# Mechanical.net
KiCad netlist of a schematic drawn in Altium Designer
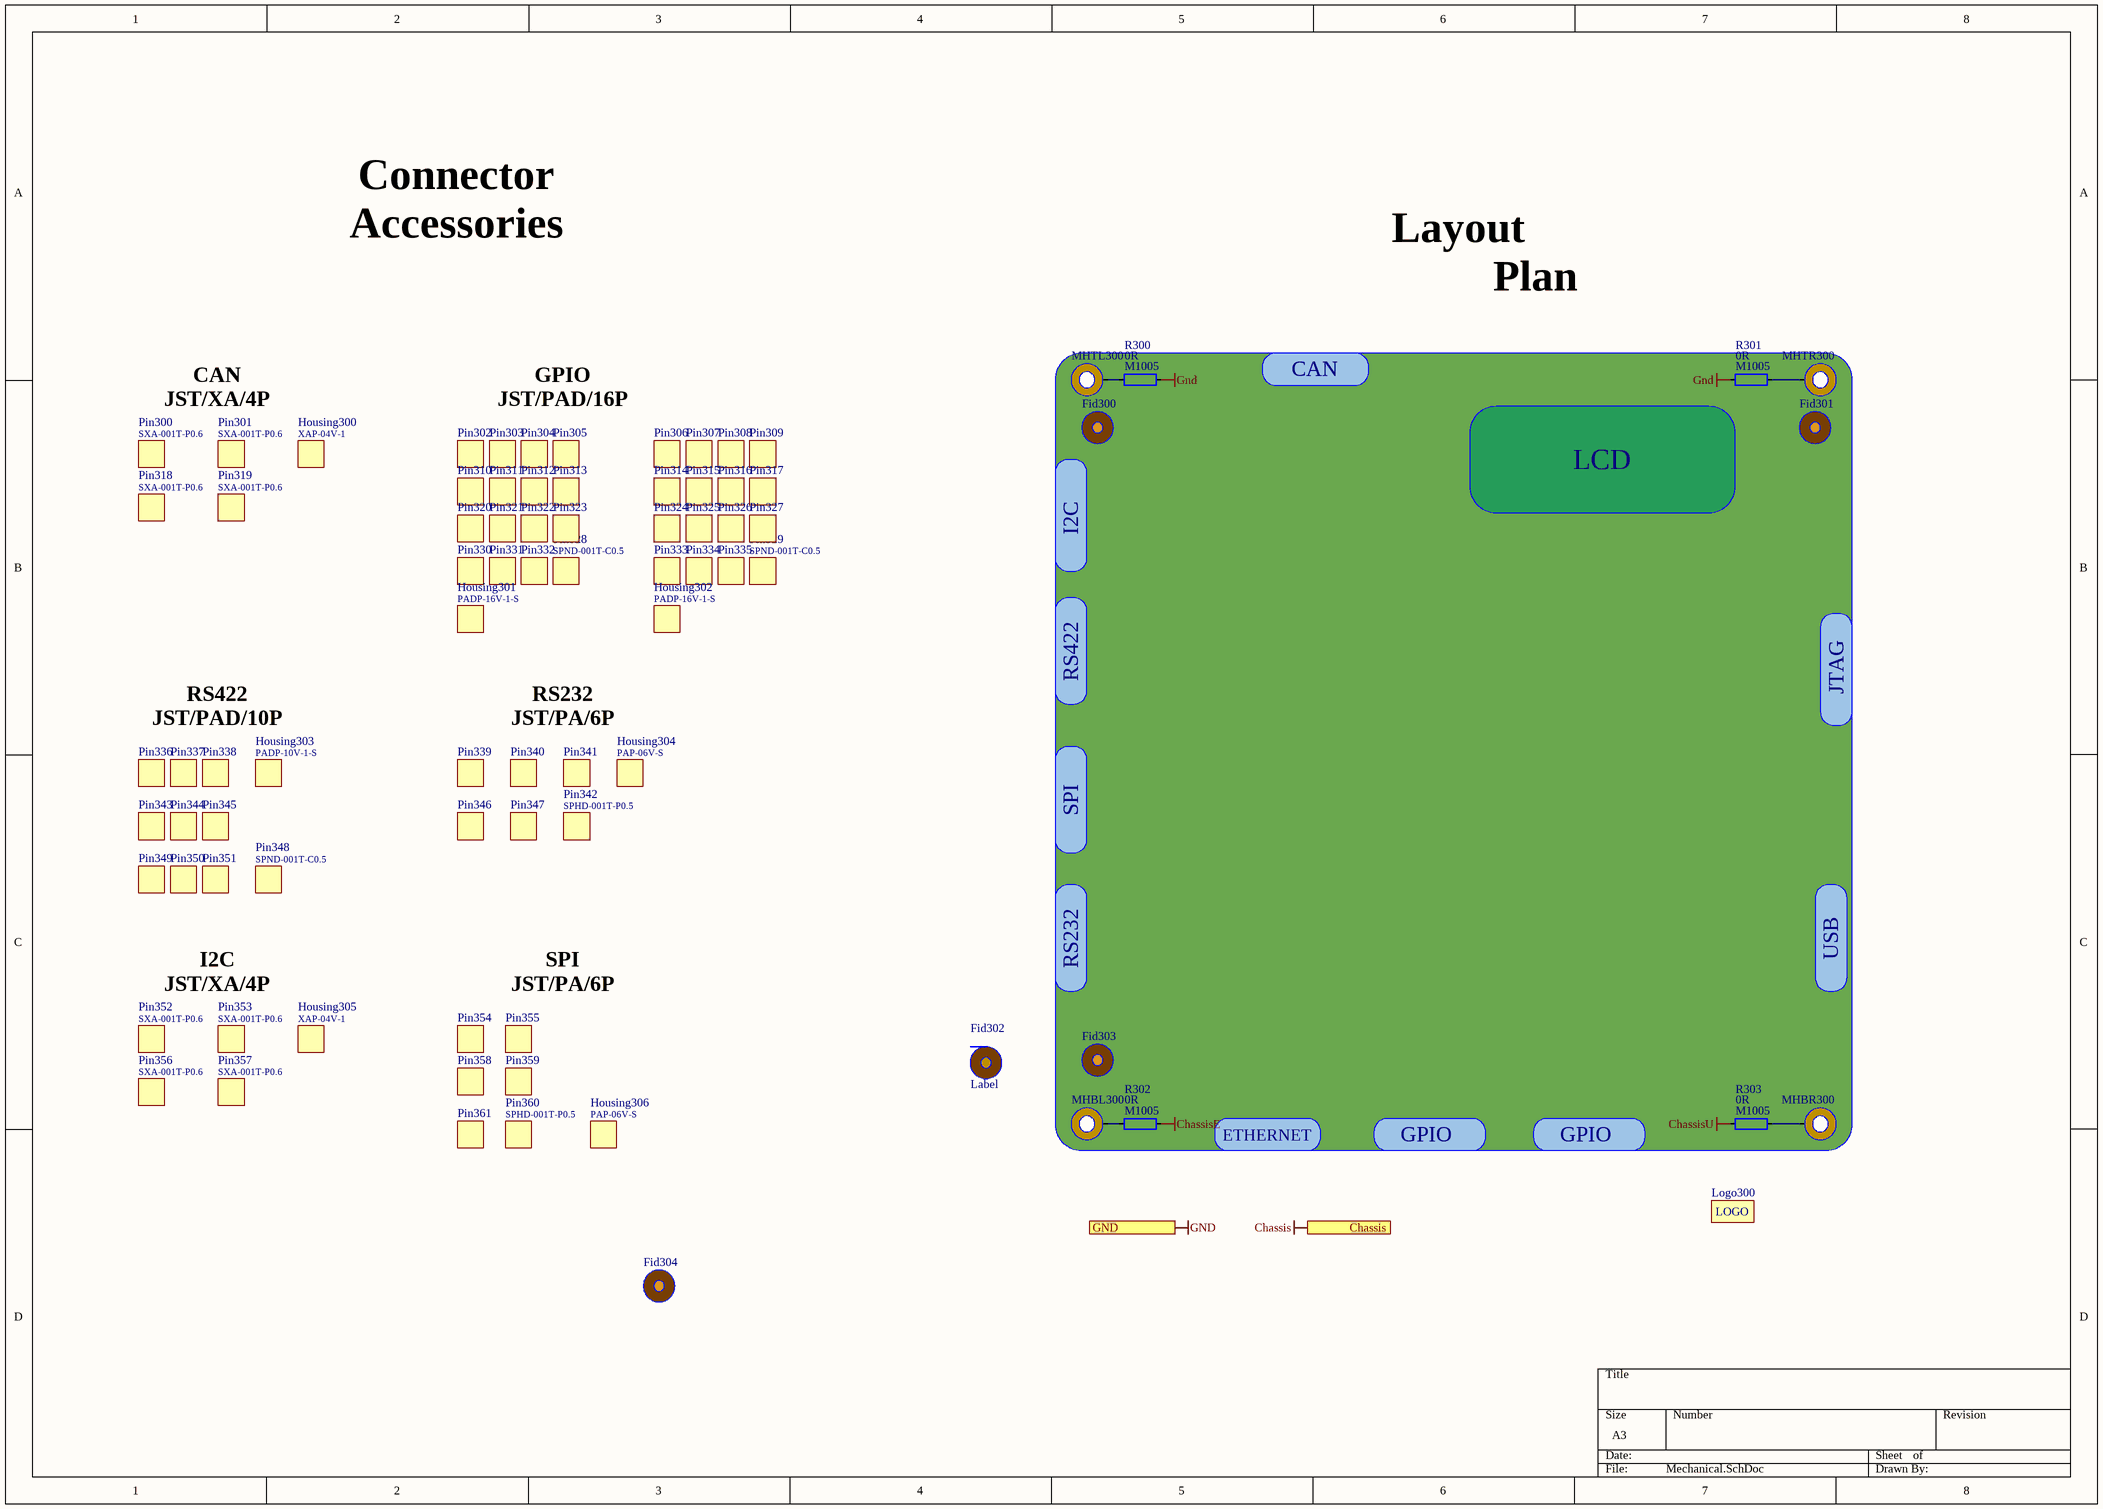
[diagram p0: Mechanical.SchDoc]

(export (version "E")
  (design (tool "Eeschema 10.0.6"))
  (components
    (comp (ref "Fid300")
      (value "Fiducial")
      (footprint "Fiducial - 2mm, 5mm")
      (description "Mechanical, Fiducial, PCB, 2mm/5mm")
      (libsource (lib "Mechanical") (part "Fiducial"))
    )
    (comp (ref "Fid301")
      (value "Fiducial")
      (footprint "Fiducial - 2mm, 5mm")
      (description "Mechanical, Fiducial, PCB, 2mm/5mm")
      (libsource (lib "Mechanical") (part "Fiducial"))
    )
    (comp (ref "Fid302")
      (value "Fiducial")
      (footprint "Fiducial-2mm,5mm")
      (description "IC,Interface,FTDI,QFN16")
      (fields (field (name "MANUFACTURER") "FTDI") (field (name "LABEL") "Label"))
      (libsource (lib "") (part "Fiducial_1"))
    )
    (comp (ref "Fid303")
      (value "Fiducial")
      (footprint "Fiducial - 2mm, 5mm")
      (description "Mechanical, Fiducial, PCB, 2mm/5mm")
      (libsource (lib "Mechanical") (part "Fiducial"))
    )
    (comp (ref "Fid304")
      (value "Fiducial")
      (footprint "Fiducial - 2mm, 5mm")
      (description "Mechanical, Fiducial, PCB, 2mm/5mm")
      (libsource (lib "Mechanical") (part "Fiducial"))
    )
    (comp (ref "Housing300")
      (value "Housing")
      (footprint "Housing, PAP-06V-S")
      (description "Housing, JST, 4P, XA")
      (fields (field (name "MANUFACTURER") "JST") (field (name "MANUFACTURER PART NUMBER") "XAP-04V-1"))
      (libsource (lib "Connector - JST") (part "Housing"))
    )
    (comp (ref "Housing301")
      (value "Housing")
      (footprint "Housing, PADP-16V-1-S")
      (description "Housing, JST, 16P, PAD")
      (fields (field (name "MANUFACTURER") "JST") (field (name "MANUFACTURER PART NUMBER") "PADP-16V-1-S"))
      (libsource (lib "Connector - JST") (part "Housing"))
    )
    (comp (ref "Housing302")
      (value "Housing")
      (footprint "Housing, PADP-16V-1-S")
      (description "Housing, JST, 16P, PAD")
      (fields (field (name "MANUFACTURER") "JST") (field (name "MANUFACTURER PART NUMBER") "PADP-16V-1-S"))
      (libsource (lib "Connector - JST") (part "Housing"))
    )
    (comp (ref "Housing303")
      (value "Housing")
      (footprint "Housing, PADP-10V-1-S")
      (description "Housing, JST, 10P, PAD")
      (fields (field (name "MANUFACTURER") "JST") (field (name "MANUFACTURER PART NUMBER") "PADP-10V-1-S"))
      (libsource (lib "Connector - JST") (part "Housing"))
    )
    (comp (ref "Housing304")
      (value "Housing")
      (footprint "Housing, PAP-06V-S")
      (description "Housing, JST, PAP-06V-S")
      (fields (field (name "MANUFACTURER") "JST") (field (name "MANUFACTURER PART NUMBER") "PAP-06V-S"))
      (libsource (lib "Connector - JST") (part "Housing"))
    )
    (comp (ref "Housing305")
      (value "Housing")
      (footprint "Housing, PAP-06V-S")
      (description "Housing, JST, 4P, XA")
      (fields (field (name "MANUFACTURER") "JST") (field (name "MANUFACTURER PART NUMBER") "XAP-04V-1"))
      (libsource (lib "Connector - JST") (part "Housing"))
    )
    (comp (ref "Housing306")
      (value "Housing")
      (footprint "Housing, PAP-06V-S")
      (description "IC, Interface, FTDI, QFN-16")
      (fields (field (name "MANUFACTURER") "JST") (field (name "MANUFACTURER PART NUMBER") "PAP-06V-S"))
      (libsource (lib "Connector - JST") (part "Housing"))
    )
    (comp (ref "Logo300")
      (value "Logo")
      (footprint "Logo 1")
      (description "Mechanical, Logo")
      (libsource (lib "Mechanical") (part "Logo"))
    )
    (comp (ref "MHBL300")
      (value "Mounting Hole")
      (footprint "Mounting Hole - Hole-3.2mm, Pad-5mm")
      (description "Mechanical, Mounting Hole")
      (libsource (lib "Mechanical") (part "Mounting Hole"))
    )
    (comp (ref "MHBR300")
      (value "Mounting Hole")
      (footprint "Mounting Hole - Hole-3.2mm, Pad-5mm")
      (description "Mechanical, Mounting Hole")
      (libsource (lib "Mechanical") (part "Mounting Hole"))
    )
    (comp (ref "MHTL300")
      (value "Mounting Hole")
      (footprint "Mounting Hole - Hole-3.2mm, Pad-5mm")
      (description "Mechanical, Mounting Hole")
      (libsource (lib "Mechanical") (part "Mounting Hole"))
    )
    (comp (ref "MHTR300")
      (value "Mounting Hole")
      (footprint "Mounting Hole - Hole-3.2mm, Pad-5mm")
      (description "Mechanical, Mounting Hole")
      (libsource (lib "Mechanical") (part "Mounting Hole"))
    )
    (comp (ref "Pin300")
      (value "Pin")
      (footprint "Pin, SPHD-001T-P0.5")
      (description "Pin, JST, SXA-001T-P0.6")
      (fields (field (name "MANUFACTURER") "JST") (field (name "MANUFACTURER PART NUMBER") "SXA-001T-P0.6"))
      (libsource (lib "Connector - JST") (part "Pin"))
    )
    (comp (ref "Pin301")
      (value "Pin")
      (footprint "Pin, SPHD-001T-P0.5")
      (description "Pin, JST, SXA-001T-P0.6")
      (fields (field (name "MANUFACTURER") "JST") (field (name "MANUFACTURER PART NUMBER") "SXA-001T-P0.6"))
      (libsource (lib "Connector - JST") (part "Pin"))
    )
    (comp (ref "Pin302")
      (value "Pin")
      (footprint "Pin, SPND-001T-C0.5")
      (description "Pin, JST, SPND-001T-C0.5")
      (fields (field (name "MANUFACTURER") "JST") (field (name "MANUFACTURER PART NUMBER") "SPND-001T-C0.5"))
      (libsource (lib "Connector - JST") (part "Pin"))
    )
    (comp (ref "Pin303")
      (value "Pin")
      (footprint "Pin, SPND-001T-C0.5")
      (description "Pin, JST, SPND-001T-C0.5")
      (fields (field (name "MANUFACTURER") "JST") (field (name "MANUFACTURER PART NUMBER") "SPND-001T-C0.5"))
      (libsource (lib "Connector - JST") (part "Pin"))
    )
    (comp (ref "Pin304")
      (value "Pin")
      (footprint "Pin, SPND-001T-C0.5")
      (description "Pin, JST, SPND-001T-C0.5")
      (fields (field (name "MANUFACTURER") "JST") (field (name "MANUFACTURER PART NUMBER") "SPND-001T-C0.5"))
      (libsource (lib "Connector - JST") (part "Pin"))
    )
    (comp (ref "Pin305")
      (value "Pin")
      (footprint "Pin, SPND-001T-C0.5")
      (description "Pin, JST, SPND-001T-C0.5")
      (fields (field (name "MANUFACTURER") "JST") (field (name "MANUFACTURER PART NUMBER") "SPND-001T-C0.5"))
      (libsource (lib "Connector - JST") (part "Pin"))
    )
    (comp (ref "Pin306")
      (value "Pin")
      (footprint "Pin, SPND-001T-C0.5")
      (description "Pin, JST, SPND-001T-C0.5")
      (fields (field (name "MANUFACTURER") "JST") (field (name "MANUFACTURER PART NUMBER") "SPND-001T-C0.5"))
      (libsource (lib "Connector - JST") (part "Pin"))
    )
    (comp (ref "Pin307")
      (value "Pin")
      (footprint "Pin, SPND-001T-C0.5")
      (description "Pin, JST, SPND-001T-C0.5")
      (fields (field (name "MANUFACTURER") "JST") (field (name "MANUFACTURER PART NUMBER") "SPND-001T-C0.5"))
      (libsource (lib "Connector - JST") (part "Pin"))
    )
    (comp (ref "Pin308")
      (value "Pin")
      (footprint "Pin, SPND-001T-C0.5")
      (description "Pin, JST, SPND-001T-C0.5")
      (fields (field (name "MANUFACTURER") "JST") (field (name "MANUFACTURER PART NUMBER") "SPND-001T-C0.5"))
      (libsource (lib "Connector - JST") (part "Pin"))
    )
    (comp (ref "Pin309")
      (value "Pin")
      (footprint "Pin, SPND-001T-C0.5")
      (description "Pin, JST, SPND-001T-C0.5")
      (fields (field (name "MANUFACTURER") "JST") (field (name "MANUFACTURER PART NUMBER") "SPND-001T-C0.5"))
      (libsource (lib "Connector - JST") (part "Pin"))
    )
    (comp (ref "Pin310")
      (value "Pin")
      (footprint "Pin, SPND-001T-C0.5")
      (description "Pin, JST, SPND-001T-C0.5")
      (fields (field (name "MANUFACTURER") "JST") (field (name "MANUFACTURER PART NUMBER") "SPND-001T-C0.5"))
      (libsource (lib "Connector - JST") (part "Pin"))
    )
    (comp (ref "Pin311")
      (value "Pin")
      (footprint "Pin, SPND-001T-C0.5")
      (description "Pin, JST, SPND-001T-C0.5")
      (fields (field (name "MANUFACTURER") "JST") (field (name "MANUFACTURER PART NUMBER") "SPND-001T-C0.5"))
      (libsource (lib "Connector - JST") (part "Pin"))
    )
    (comp (ref "Pin312")
      (value "Pin")
      (footprint "Pin, SPND-001T-C0.5")
      (description "Pin, JST, SPND-001T-C0.5")
      (fields (field (name "MANUFACTURER") "JST") (field (name "MANUFACTURER PART NUMBER") "SPND-001T-C0.5"))
      (libsource (lib "Connector - JST") (part "Pin"))
    )
    (comp (ref "Pin313")
      (value "Pin")
      (footprint "Pin, SPND-001T-C0.5")
      (description "Pin, JST, SPND-001T-C0.5")
      (fields (field (name "MANUFACTURER") "JST") (field (name "MANUFACTURER PART NUMBER") "SPND-001T-C0.5"))
      (libsource (lib "Connector - JST") (part "Pin"))
    )
    (comp (ref "Pin314")
      (value "Pin")
      (footprint "Pin, SPND-001T-C0.5")
      (description "Pin, JST, SPND-001T-C0.5")
      (fields (field (name "MANUFACTURER") "JST") (field (name "MANUFACTURER PART NUMBER") "SPND-001T-C0.5"))
      (libsource (lib "Connector - JST") (part "Pin"))
    )
    (comp (ref "Pin315")
      (value "Pin")
      (footprint "Pin, SPND-001T-C0.5")
      (description "Pin, JST, SPND-001T-C0.5")
      (fields (field (name "MANUFACTURER") "JST") (field (name "MANUFACTURER PART NUMBER") "SPND-001T-C0.5"))
      (libsource (lib "Connector - JST") (part "Pin"))
    )
    (comp (ref "Pin316")
      (value "Pin")
      (footprint "Pin, SPND-001T-C0.5")
      (description "Pin, JST, SPND-001T-C0.5")
      (fields (field (name "MANUFACTURER") "JST") (field (name "MANUFACTURER PART NUMBER") "SPND-001T-C0.5"))
      (libsource (lib "Connector - JST") (part "Pin"))
    )
    (comp (ref "Pin317")
      (value "Pin")
      (footprint "Pin, SPND-001T-C0.5")
      (description "Pin, JST, SPND-001T-C0.5")
      (fields (field (name "MANUFACTURER") "JST") (field (name "MANUFACTURER PART NUMBER") "SPND-001T-C0.5"))
      (libsource (lib "Connector - JST") (part "Pin"))
    )
    (comp (ref "Pin318")
      (value "Pin")
      (footprint "Pin, SPHD-001T-P0.5")
      (description "Pin, JST, SXA-001T-P0.6")
      (fields (field (name "MANUFACTURER") "JST") (field (name "MANUFACTURER PART NUMBER") "SXA-001T-P0.6"))
      (libsource (lib "Connector - JST") (part "Pin"))
    )
    (comp (ref "Pin319")
      (value "Pin")
      (footprint "Pin, SPHD-001T-P0.5")
      (description "Pin, JST, SXA-001T-P0.6")
      (fields (field (name "MANUFACTURER") "JST") (field (name "MANUFACTURER PART NUMBER") "SXA-001T-P0.6"))
      (libsource (lib "Connector - JST") (part "Pin"))
    )
    (comp (ref "Pin320")
      (value "Pin")
      (footprint "Pin, SPND-001T-C0.5")
      (description "Pin, JST, SPND-001T-C0.5")
      (fields (field (name "MANUFACTURER") "JST") (field (name "MANUFACTURER PART NUMBER") "SPND-001T-C0.5"))
      (libsource (lib "Connector - JST") (part "Pin"))
    )
    (comp (ref "Pin321")
      (value "Pin")
      (footprint "Pin, SPND-001T-C0.5")
      (description "Pin, JST, SPND-001T-C0.5")
      (fields (field (name "MANUFACTURER") "JST") (field (name "MANUFACTURER PART NUMBER") "SPND-001T-C0.5"))
      (libsource (lib "Connector - JST") (part "Pin"))
    )
    (comp (ref "Pin322")
      (value "Pin")
      (footprint "Pin, SPND-001T-C0.5")
      (description "Pin, JST, SPND-001T-C0.5")
      (fields (field (name "MANUFACTURER") "JST") (field (name "MANUFACTURER PART NUMBER") "SPND-001T-C0.5"))
      (libsource (lib "Connector - JST") (part "Pin"))
    )
    (comp (ref "Pin323")
      (value "Pin")
      (footprint "Pin, SPND-001T-C0.5")
      (description "Pin, JST, SPND-001T-C0.5")
      (fields (field (name "MANUFACTURER") "JST") (field (name "MANUFACTURER PART NUMBER") "SPND-001T-C0.5"))
      (libsource (lib "Connector - JST") (part "Pin"))
    )
    (comp (ref "Pin324")
      (value "Pin")
      (footprint "Pin, SPND-001T-C0.5")
      (description "Pin, JST, SPND-001T-C0.5")
      (fields (field (name "MANUFACTURER") "JST") (field (name "MANUFACTURER PART NUMBER") "SPND-001T-C0.5"))
      (libsource (lib "Connector - JST") (part "Pin"))
    )
    (comp (ref "Pin325")
      (value "Pin")
      (footprint "Pin, SPND-001T-C0.5")
      (description "Pin, JST, SPND-001T-C0.5")
      (fields (field (name "MANUFACTURER") "JST") (field (name "MANUFACTURER PART NUMBER") "SPND-001T-C0.5"))
      (libsource (lib "Connector - JST") (part "Pin"))
    )
    (comp (ref "Pin326")
      (value "Pin")
      (footprint "Pin, SPND-001T-C0.5")
      (description "Pin, JST, SPND-001T-C0.5")
      (fields (field (name "MANUFACTURER") "JST") (field (name "MANUFACTURER PART NUMBER") "SPND-001T-C0.5"))
      (libsource (lib "Connector - JST") (part "Pin"))
    )
    (comp (ref "Pin327")
      (value "Pin")
      (footprint "Pin, SPND-001T-C0.5")
      (description "Pin, JST, SPND-001T-C0.5")
      (fields (field (name "MANUFACTURER") "JST") (field (name "MANUFACTURER PART NUMBER") "SPND-001T-C0.5"))
      (libsource (lib "Connector - JST") (part "Pin"))
    )
    (comp (ref "Pin328")
      (value "Pin")
      (footprint "Pin, SPND-001T-C0.5")
      (description "Pin, JST, SPND-001T-C0.5")
      (fields (field (name "MANUFACTURER") "JST") (field (name "MANUFACTURER PART NUMBER") "SPND-001T-C0.5"))
      (libsource (lib "Connector - JST") (part "Pin"))
    )
    (comp (ref "Pin329")
      (value "Pin")
      (footprint "Pin, SPND-001T-C0.5")
      (description "Pin, JST, SPND-001T-C0.5")
      (fields (field (name "MANUFACTURER") "JST") (field (name "MANUFACTURER PART NUMBER") "SPND-001T-C0.5"))
      (libsource (lib "Connector - JST") (part "Pin"))
    )
    (comp (ref "Pin330")
      (value "Pin")
      (footprint "Pin, SPND-001T-C0.5")
      (description "Pin, JST, SPND-001T-C0.5")
      (fields (field (name "MANUFACTURER") "JST") (field (name "MANUFACTURER PART NUMBER") "SPND-001T-C0.5"))
      (libsource (lib "Connector - JST") (part "Pin"))
    )
    (comp (ref "Pin331")
      (value "Pin")
      (footprint "Pin, SPND-001T-C0.5")
      (description "Pin, JST, SPND-001T-C0.5")
      (fields (field (name "MANUFACTURER") "JST") (field (name "MANUFACTURER PART NUMBER") "SPND-001T-C0.5"))
      (libsource (lib "Connector - JST") (part "Pin"))
    )
    (comp (ref "Pin332")
      (value "Pin")
      (footprint "Pin, SPND-001T-C0.5")
      (description "Pin, JST, SPND-001T-C0.5")
      (fields (field (name "MANUFACTURER") "JST") (field (name "MANUFACTURER PART NUMBER") "SPND-001T-C0.5"))
      (libsource (lib "Connector - JST") (part "Pin"))
    )
    (comp (ref "Pin333")
      (value "Pin")
      (footprint "Pin, SPND-001T-C0.5")
      (description "Pin, JST, SPND-001T-C0.5")
      (fields (field (name "MANUFACTURER") "JST") (field (name "MANUFACTURER PART NUMBER") "SPND-001T-C0.5"))
      (libsource (lib "Connector - JST") (part "Pin"))
    )
    (comp (ref "Pin334")
      (value "Pin")
      (footprint "Pin, SPND-001T-C0.5")
      (description "Pin, JST, SPND-001T-C0.5")
      (fields (field (name "MANUFACTURER") "JST") (field (name "MANUFACTURER PART NUMBER") "SPND-001T-C0.5"))
      (libsource (lib "Connector - JST") (part "Pin"))
    )
    (comp (ref "Pin335")
      (value "Pin")
      (footprint "Pin, SPND-001T-C0.5")
      (description "Pin, JST, SPND-001T-C0.5")
      (fields (field (name "MANUFACTURER") "JST") (field (name "MANUFACTURER PART NUMBER") "SPND-001T-C0.5"))
      (libsource (lib "Connector - JST") (part "Pin"))
    )
    (comp (ref "Pin336")
      (value "Pin")
      (footprint "Pin, SPND-001T-C0.5")
      (description "Pin, JST, SPND-001T-C0.5")
      (fields (field (name "MANUFACTURER") "JST") (field (name "MANUFACTURER PART NUMBER") "SPND-001T-C0.5"))
      (libsource (lib "Connector - JST") (part "Pin"))
    )
    (comp (ref "Pin337")
      (value "Pin")
      (footprint "Pin, SPND-001T-C0.5")
      (description "Pin, JST, SPND-001T-C0.5")
      (fields (field (name "MANUFACTURER") "JST") (field (name "MANUFACTURER PART NUMBER") "SPND-001T-C0.5"))
      (libsource (lib "Connector - JST") (part "Pin"))
    )
    (comp (ref "Pin338")
      (value "Pin")
      (footprint "Pin, SPND-001T-C0.5")
      (description "Pin, JST, SPND-001T-C0.5")
      (fields (field (name "MANUFACTURER") "JST") (field (name "MANUFACTURER PART NUMBER") "SPND-001T-C0.5"))
      (libsource (lib "Connector - JST") (part "Pin"))
    )
    (comp (ref "Pin339")
      (value "Pin")
      (footprint "Pin, SPHD-001T-P0.5")
      (description "Pin, JST, SPHD-001T-P0.5")
      (fields (field (name "MANUFACTURER") "JST") (field (name "MANUFACTURER PART NUMBER") "SPHD-001T-P0.5"))
      (libsource (lib "Connector - JST") (part "Pin"))
    )
    (comp (ref "Pin340")
      (value "Pin")
      (footprint "Pin, SPHD-001T-P0.5")
      (description "Pin, JST, SPHD-001T-P0.5")
      (fields (field (name "MANUFACTURER") "JST") (field (name "MANUFACTURER PART NUMBER") "SPHD-001T-P0.5"))
      (libsource (lib "Connector - JST") (part "Pin"))
    )
    (comp (ref "Pin341")
      (value "Pin")
      (footprint "Pin, SPHD-001T-P0.5")
      (description "Pin, JST, SPHD-001T-P0.5")
      (fields (field (name "MANUFACTURER") "JST") (field (name "MANUFACTURER PART NUMBER") "SPHD-001T-P0.5"))
      (libsource (lib "Connector - JST") (part "Pin"))
    )
    (comp (ref "Pin342")
      (value "Pin")
      (footprint "Pin, SPHD-001T-P0.5")
      (description "Pin, JST, SPHD-001T-P0.5")
      (fields (field (name "MANUFACTURER") "JST") (field (name "MANUFACTURER PART NUMBER") "SPHD-001T-P0.5"))
      (libsource (lib "Connector - JST") (part "Pin"))
    )
    (comp (ref "Pin343")
      (value "Pin")
      (footprint "Pin, SPND-001T-C0.5")
      (description "Pin, JST, SPND-001T-C0.5")
      (fields (field (name "MANUFACTURER") "JST") (field (name "MANUFACTURER PART NUMBER") "SPND-001T-C0.5"))
      (libsource (lib "Connector - JST") (part "Pin"))
    )
    (comp (ref "Pin344")
      (value "Pin")
      (footprint "Pin, SPND-001T-C0.5")
      (description "Pin, JST, SPND-001T-C0.5")
      (fields (field (name "MANUFACTURER") "JST") (field (name "MANUFACTURER PART NUMBER") "SPND-001T-C0.5"))
      (libsource (lib "Connector - JST") (part "Pin"))
    )
    (comp (ref "Pin345")
      (value "Pin")
      (footprint "Pin, SPND-001T-C0.5")
      (description "Pin, JST, SPND-001T-C0.5")
      (fields (field (name "MANUFACTURER") "JST") (field (name "MANUFACTURER PART NUMBER") "SPND-001T-C0.5"))
      (libsource (lib "Connector - JST") (part "Pin"))
    )
    (comp (ref "Pin346")
      (value "Pin")
      (footprint "Pin, SPHD-001T-P0.5")
      (description "Pin, JST, SPHD-001T-P0.5")
      (fields (field (name "MANUFACTURER") "JST") (field (name "MANUFACTURER PART NUMBER") "SPHD-001T-P0.5"))
      (libsource (lib "Connector - JST") (part "Pin"))
    )
    (comp (ref "Pin347")
      (value "Pin")
      (footprint "Pin, SPHD-001T-P0.5")
      (description "Pin, JST, SPHD-001T-P0.5")
      (fields (field (name "MANUFACTURER") "JST") (field (name "MANUFACTURER PART NUMBER") "SPHD-001T-P0.5"))
      (libsource (lib "Connector - JST") (part "Pin"))
    )
    (comp (ref "Pin348")
      (value "Pin")
      (footprint "Pin, SPND-001T-C0.5")
      (description "Pin, JST, SPND-001T-C0.5")
      (fields (field (name "MANUFACTURER") "JST") (field (name "MANUFACTURER PART NUMBER") "SPND-001T-C0.5"))
      (libsource (lib "Connector - JST") (part "Pin"))
    )
    (comp (ref "Pin349")
      (value "Pin")
      (footprint "Pin, SPND-001T-C0.5")
      (description "Pin, JST, SPND-001T-C0.5")
      (fields (field (name "MANUFACTURER") "JST") (field (name "MANUFACTURER PART NUMBER") "SPND-001T-C0.5"))
      (libsource (lib "Connector - JST") (part "Pin"))
    )
    (comp (ref "Pin350")
      (value "Pin")
      (footprint "Pin, SPND-001T-C0.5")
      (description "Pin, JST, SPND-001T-C0.5")
      (fields (field (name "MANUFACTURER") "JST") (field (name "MANUFACTURER PART NUMBER") "SPND-001T-C0.5"))
      (libsource (lib "Connector - JST") (part "Pin"))
    )
    (comp (ref "Pin351")
      (value "Pin")
      (footprint "Pin, SPND-001T-C0.5")
      (description "Pin, JST, SPND-001T-C0.5")
      (fields (field (name "MANUFACTURER") "JST") (field (name "MANUFACTURER PART NUMBER") "SPND-001T-C0.5"))
      (libsource (lib "Connector - JST") (part "Pin"))
    )
    (comp (ref "Pin352")
      (value "Pin")
      (footprint "Pin, SPHD-001T-P0.5")
      (description "Pin, JST, SXA-001T-P0.6")
      (fields (field (name "MANUFACTURER") "JST") (field (name "MANUFACTURER PART NUMBER") "SXA-001T-P0.6"))
      (libsource (lib "Connector - JST") (part "Pin"))
    )
    (comp (ref "Pin353")
      (value "Pin")
      (footprint "Pin, SPHD-001T-P0.5")
      (description "Pin, JST, SXA-001T-P0.6")
      (fields (field (name "MANUFACTURER") "JST") (field (name "MANUFACTURER PART NUMBER") "SXA-001T-P0.6"))
      (libsource (lib "Connector - JST") (part "Pin"))
    )
    (comp (ref "Pin354")
      (value "Pin")
      (footprint "Pin, SPHD-001T-P0.5")
      (description "IC, Interface, FTDI, QFN-16")
      (fields (field (name "MANUFACTURER") "JST") (field (name "MANUFACTURER PART NUMBER") "SPHD-001T-P0.5"))
      (libsource (lib "Connector - JST") (part "Pin"))
    )
    (comp (ref "Pin355")
      (value "Pin")
      (footprint "Pin, SPHD-001T-P0.5")
      (description "IC, Interface, FTDI, QFN-16")
      (fields (field (name "MANUFACTURER") "JST") (field (name "MANUFACTURER PART NUMBER") "SPHD-001T-P0.5"))
      (libsource (lib "Connector - JST") (part "Pin"))
    )
    (comp (ref "Pin356")
      (value "Pin")
      (footprint "Pin, SPHD-001T-P0.5")
      (description "Pin, JST, SXA-001T-P0.6")
      (fields (field (name "MANUFACTURER") "JST") (field (name "MANUFACTURER PART NUMBER") "SXA-001T-P0.6"))
      (libsource (lib "Connector - JST") (part "Pin"))
    )
    (comp (ref "Pin357")
      (value "Pin")
      (footprint "Pin, SPHD-001T-P0.5")
      (description "Pin, JST, SXA-001T-P0.6")
      (fields (field (name "MANUFACTURER") "JST") (field (name "MANUFACTURER PART NUMBER") "SXA-001T-P0.6"))
      (libsource (lib "Connector - JST") (part "Pin"))
    )
    (comp (ref "Pin358")
      (value "Pin")
      (footprint "Pin, SPHD-001T-P0.5")
      (description "IC, Interface, FTDI, QFN-16")
      (fields (field (name "MANUFACTURER") "JST") (field (name "MANUFACTURER PART NUMBER") "SPHD-001T-P0.5"))
      (libsource (lib "Connector - JST") (part "Pin"))
    )
    (comp (ref "Pin359")
      (value "Pin")
      (footprint "Pin, SPHD-001T-P0.5")
      (description "IC, Interface, FTDI, QFN-16")
      (fields (field (name "MANUFACTURER") "JST") (field (name "MANUFACTURER PART NUMBER") "SPHD-001T-P0.5"))
      (libsource (lib "Connector - JST") (part "Pin"))
    )
    (comp (ref "Pin360")
      (value "Pin")
      (footprint "Pin, SPHD-001T-P0.5")
      (description "IC, Interface, FTDI, QFN-16")
      (fields (field (name "MANUFACTURER") "JST") (field (name "MANUFACTURER PART NUMBER") "SPHD-001T-P0.5"))
      (libsource (lib "Connector - JST") (part "Pin"))
    )
    (comp (ref "Pin361")
      (value "Pin")
      (footprint "Pin, SPHD-001T-P0.5")
      (description "IC, Interface, FTDI, QFN-16")
      (fields (field (name "MANUFACTURER") "JST") (field (name "MANUFACTURER PART NUMBER") "SPHD-001T-P0.5"))
      (libsource (lib "Connector - JST") (part "Pin"))
    )
    (comp (ref "R300")
      (value "0R")
      (footprint "Resistor_Smd_M1005_I0402")
      (description "Res, 0R, M1005")
      (fields
        (field (name "MANUFACTURER") "Yageo")
        (field (name "MANUFACTURER PART NUMBER") "RC0402FR-070RL")
        (field (name "PACKAGE") "M1005")
      )
      (libsource (lib "Resistor") (part "Resistor"))
    )
    (comp (ref "R301")
      (value "0R")
      (footprint "Resistor_Smd_M1005_I0402")
      (description "Res, 0R, M1005")
      (fields
        (field (name "MANUFACTURER") "Yageo")
        (field (name "MANUFACTURER PART NUMBER") "RC0402FR-070RL")
        (field (name "PACKAGE") "M1005")
      )
      (libsource (lib "Resistor") (part "Resistor"))
    )
    (comp (ref "R302")
      (value "0R")
      (footprint "Resistor_Smd_M1005_I0402")
      (description "Res, 0R, M1005")
      (fields
        (field (name "MANUFACTURER") "Yageo")
        (field (name "MANUFACTURER PART NUMBER") "RC0402FR-070RL")
        (field (name "PACKAGE") "M1005")
      )
      (libsource (lib "Resistor") (part "Resistor"))
    )
    (comp (ref "R303")
      (value "0R")
      (footprint "Resistor_Smd_M1005_I0402")
      (description "Res, 0R, M1005")
      (fields
        (field (name "MANUFACTURER") "Yageo")
        (field (name "MANUFACTURER PART NUMBER") "RC0402FR-070RL")
        (field (name "PACKAGE") "M1005")
      )
      (libsource (lib "Resistor") (part "Resistor"))
    )
  )
  (nets
    (net (code "2") (name "ChassisE") (class "Default")
      (node (ref "R302") (pin "2") (pinfunction "2_2") (pintype "passive"))
    )
    (net (code "3") (name "ChassisU") (class "Default")
      (node (ref "R303") (pin "1") (pinfunction "1_1") (pintype "passive"))
    )
    (net (code "5") (name "Gnd") (class "Default")
      (node (ref "R300") (pin "2") (pinfunction "2_2") (pintype "passive"))
      (node (ref "R301") (pin "1") (pinfunction "1_1") (pintype "passive"))
    )
    (net (code "6") (name "Net-(MHBL300-PadHole)") (class "Default")
      (node (ref "MHBL300") (pin "Hole") (pinfunction "Hole_Hole") (pintype "passive"))
      (node (ref "R302") (pin "1") (pinfunction "1_1") (pintype "passive"))
    )
    (net (code "7") (name "Net-(MHBR300-PadHole)") (class "Default")
      (node (ref "MHBR300") (pin "Hole") (pinfunction "Hole_Hole") (pintype "passive"))
      (node (ref "R303") (pin "2") (pinfunction "2_2") (pintype "passive"))
    )
    (net (code "8") (name "Net-(MHTL300-PadHole)") (class "Default")
      (node (ref "MHTL300") (pin "Hole") (pinfunction "Hole_Hole") (pintype "passive"))
      (node (ref "R300") (pin "1") (pinfunction "1_1") (pintype "passive"))
    )
    (net (code "9") (name "Net-(MHTR300-PadHole)") (class "Default")
      (node (ref "MHTR300") (pin "Hole") (pinfunction "Hole_Hole") (pintype "passive"))
      (node (ref "R301") (pin "2") (pinfunction "2_2") (pintype "passive"))
    )
  )
)
